# xc7z015unit3.net
KiCad netlist of a schematic drawn in Altium Designer
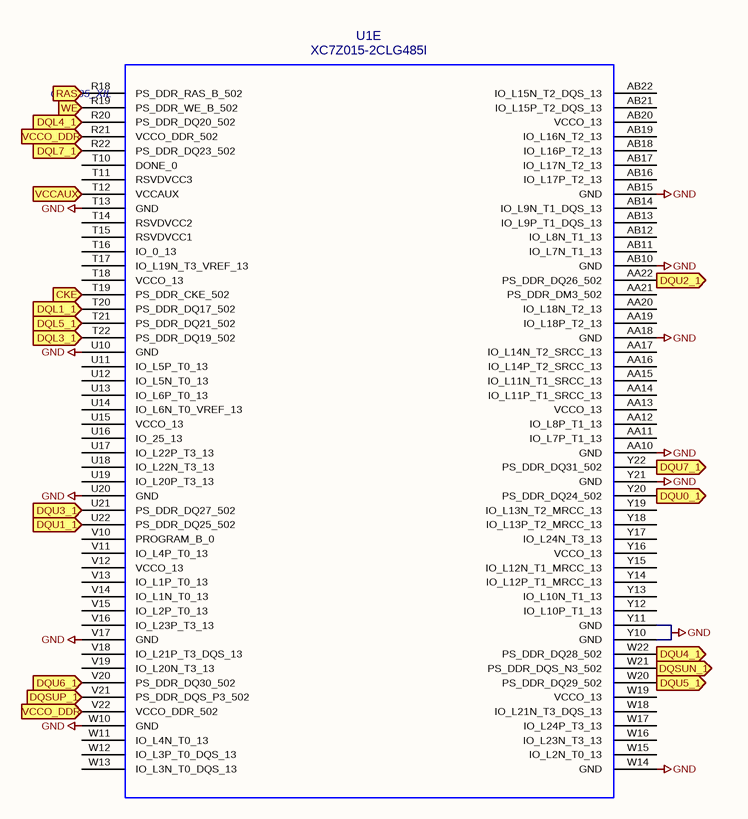
[diagram p0: xc7z015unit3.SchDoc]

(export (version "E")
  (design (tool "Eeschema 10.0.6"))
  (components
    (comp (ref "U1")
      (value "XC7Z015-2CLG485I")
      (footprint "CLG485_XIL")
      (libsource (lib "XC7Z015-CLG485") (part "XC7Z015-2CLG485I"))
    )
  )
  (nets
    (net (code "1") (name "/CKE") (class "Default")
      (node (ref "U1") (pin "T19") (pinfunction "PS_DDR_CKE_502_T19") (pintype "passive"))
    )
    (net (code "2") (name "/DQL1_1") (class "Default")
      (node (ref "U1") (pin "T20") (pinfunction "PS_DDR_DQ17_502_T20") (pintype "passive"))
    )
    (net (code "3") (name "/DQL3_1") (class "Default")
      (node (ref "U1") (pin "T22") (pinfunction "PS_DDR_DQ19_502_T22") (pintype "passive"))
    )
    (net (code "4") (name "/DQL4_1") (class "Default")
      (node (ref "U1") (pin "R20") (pinfunction "PS_DDR_DQ20_502_R20") (pintype "passive"))
    )
    (net (code "5") (name "/DQL5_1") (class "Default")
      (node (ref "U1") (pin "T21") (pinfunction "PS_DDR_DQ21_502_T21") (pintype "passive"))
    )
    (net (code "6") (name "/DQL7_1") (class "Default")
      (node (ref "U1") (pin "R22") (pinfunction "PS_DDR_DQ23_502_R22") (pintype "passive"))
    )
    (net (code "7") (name "/DQSUN_1") (class "Default")
      (node (ref "U1") (pin "W21") (pinfunction "PS_DDR_DQS_N3_502_W21") (pintype "passive"))
    )
    (net (code "8") (name "/DQSUP_1") (class "Default")
      (node (ref "U1") (pin "V21") (pinfunction "PS_DDR_DQS_P3_502_V21") (pintype "passive"))
    )
    (net (code "9") (name "/DQU0_1") (class "Default")
      (node (ref "U1") (pin "Y20") (pinfunction "PS_DDR_DQ24_502_Y20") (pintype "passive"))
    )
    (net (code "10") (name "/DQU1_1") (class "Default")
      (node (ref "U1") (pin "U22") (pinfunction "PS_DDR_DQ25_502_U22") (pintype "passive"))
    )
    (net (code "11") (name "/DQU2_1") (class "Default")
      (node (ref "U1") (pin "AA22") (pinfunction "PS_DDR_DQ26_502_AA22") (pintype "passive"))
    )
    (net (code "12") (name "/DQU3_1") (class "Default")
      (node (ref "U1") (pin "U21") (pinfunction "PS_DDR_DQ27_502_U21") (pintype "passive"))
    )
    (net (code "13") (name "/DQU4_1") (class "Default")
      (node (ref "U1") (pin "W22") (pinfunction "PS_DDR_DQ28_502_W22") (pintype "passive"))
    )
    (net (code "14") (name "/DQU5_1") (class "Default")
      (node (ref "U1") (pin "W20") (pinfunction "PS_DDR_DQ29_502_W20") (pintype "passive"))
    )
    (net (code "15") (name "/DQU6_1") (class "Default")
      (node (ref "U1") (pin "V20") (pinfunction "PS_DDR_DQ30_502_V20") (pintype "passive"))
    )
    (net (code "16") (name "/DQU7_1") (class "Default")
      (node (ref "U1") (pin "Y22") (pinfunction "PS_DDR_DQ31_502_Y22") (pintype "passive"))
    )
    (net (code "17") (name "/RAS") (class "Default")
      (node (ref "U1") (pin "R18") (pinfunction "PS_DDR_RAS_B_502_R18") (pintype "passive"))
    )
    (net (code "18") (name "/VCCAUX") (class "Default")
      (node (ref "U1") (pin "T12") (pinfunction "VCCAUX_T12") (pintype "passive"))
    )
    (net (code "19") (name "/VCCO_DDR") (class "Default")
      (node (ref "U1") (pin "R21") (pinfunction "VCCO_DDR_502_R21") (pintype "passive"))
      (node (ref "U1") (pin "V22") (pinfunction "VCCO_DDR_502_V22") (pintype "passive"))
    )
    (net (code "20") (name "/WE") (class "Default")
      (node (ref "U1") (pin "R19") (pinfunction "PS_DDR_WE_B_502_R19") (pintype "passive"))
    )
    (net (code "21") (name "GND") (class "Default")
      (node (ref "U1") (pin "AA10") (pinfunction "GND_AA10") (pintype "passive"))
      (node (ref "U1") (pin "AA18") (pinfunction "GND_AA18") (pintype "passive"))
      (node (ref "U1") (pin "AB10") (pinfunction "GND_AB10") (pintype "passive"))
      (node (ref "U1") (pin "AB15") (pinfunction "GND_AB15") (pintype "passive"))
      (node (ref "U1") (pin "T13") (pinfunction "GND_T13") (pintype "passive"))
      (node (ref "U1") (pin "U10") (pinfunction "GND_U10") (pintype "passive"))
      (node (ref "U1") (pin "U20") (pinfunction "GND_U20") (pintype "passive"))
      (node (ref "U1") (pin "V17") (pinfunction "GND_V17") (pintype "passive"))
      (node (ref "U1") (pin "W10") (pinfunction "GND_W10") (pintype "passive"))
      (node (ref "U1") (pin "W14") (pinfunction "GND_W14") (pintype "passive"))
      (node (ref "U1") (pin "Y10") (pinfunction "GND_Y10") (pintype "passive"))
      (node (ref "U1") (pin "Y11") (pinfunction "GND_Y11") (pintype "passive"))
      (node (ref "U1") (pin "Y21") (pinfunction "GND_Y21") (pintype "passive"))
    )
    (net (code "22") (name "unconnected-(U1E-DONE_0-PadT10)") (class "Default")
      (node (ref "U1") (pin "T10") (pinfunction "DONE_0_T10") (pintype "passive"))
    )
    (net (code "23") (name "unconnected-(U1E-IO_0_13-PadT16)") (class "Default")
      (node (ref "U1") (pin "T16") (pinfunction "IO_0_13_T16") (pintype "passive"))
    )
    (net (code "24") (name "unconnected-(U1E-IO_25_13-PadU16)") (class "Default")
      (node (ref "U1") (pin "U16") (pinfunction "IO_25_13_U16") (pintype "passive"))
    )
    (net (code "25") (name "unconnected-(U1E-IO_L1N_T0_13-PadV14)") (class "Default")
      (node (ref "U1") (pin "V14") (pinfunction "IO_L1N_T0_13_V14") (pintype "passive"))
    )
    (net (code "26") (name "unconnected-(U1E-IO_L1P_T0_13-PadV13)") (class "Default")
      (node (ref "U1") (pin "V13") (pinfunction "IO_L1P_T0_13_V13") (pintype "passive"))
    )
    (net (code "27") (name "unconnected-(U1E-IO_L2N_T0_13-PadW15)") (class "Default")
      (node (ref "U1") (pin "W15") (pinfunction "IO_L2N_T0_13_W15") (pintype "passive"))
    )
    (net (code "28") (name "unconnected-(U1E-IO_L2P_T0_13-PadV15)") (class "Default")
      (node (ref "U1") (pin "V15") (pinfunction "IO_L2P_T0_13_V15") (pintype "passive"))
    )
    (net (code "29") (name "unconnected-(U1E-IO_L3N_T0_DQS_13-PadW13)") (class "Default")
      (node (ref "U1") (pin "W13") (pinfunction "IO_L3N_T0_DQS_13_W13") (pintype "passive"))
    )
    (net (code "30") (name "unconnected-(U1E-IO_L3P_T0_DQS_13-PadW12)") (class "Default")
      (node (ref "U1") (pin "W12") (pinfunction "IO_L3P_T0_DQS_13_W12") (pintype "passive"))
    )
    (net (code "31") (name "unconnected-(U1E-IO_L4N_T0_13-PadW11)") (class "Default")
      (node (ref "U1") (pin "W11") (pinfunction "IO_L4N_T0_13_W11") (pintype "passive"))
    )
    (net (code "32") (name "unconnected-(U1E-IO_L4P_T0_13-PadV11)") (class "Default")
      (node (ref "U1") (pin "V11") (pinfunction "IO_L4P_T0_13_V11") (pintype "passive"))
    )
    (net (code "33") (name "unconnected-(U1E-IO_L5N_T0_13-PadU12)") (class "Default")
      (node (ref "U1") (pin "U12") (pinfunction "IO_L5N_T0_13_U12") (pintype "passive"))
    )
    (net (code "34") (name "unconnected-(U1E-IO_L5P_T0_13-PadU11)") (class "Default")
      (node (ref "U1") (pin "U11") (pinfunction "IO_L5P_T0_13_U11") (pintype "passive"))
    )
    (net (code "35") (name "unconnected-(U1E-IO_L6N_T0_VREF_13-PadU14)") (class "Default")
      (node (ref "U1") (pin "U14") (pinfunction "IO_L6N_T0_VREF_13_U14") (pintype "passive"))
    )
    (net (code "36") (name "unconnected-(U1E-IO_L6P_T0_13-PadU13)") (class "Default")
      (node (ref "U1") (pin "U13") (pinfunction "IO_L6P_T0_13_U13") (pintype "passive"))
    )
    (net (code "37") (name "unconnected-(U1E-IO_L7N_T1_13-PadAB11)") (class "Default")
      (node (ref "U1") (pin "AB11") (pinfunction "IO_L7N_T1_13_AB11") (pintype "passive"))
    )
    (net (code "38") (name "unconnected-(U1E-IO_L7P_T1_13-PadAA11)") (class "Default")
      (node (ref "U1") (pin "AA11") (pinfunction "IO_L7P_T1_13_AA11") (pintype "passive"))
    )
    (net (code "39") (name "unconnected-(U1E-IO_L8N_T1_13-PadAB12)") (class "Default")
      (node (ref "U1") (pin "AB12") (pinfunction "IO_L8N_T1_13_AB12") (pintype "passive"))
    )
    (net (code "40") (name "unconnected-(U1E-IO_L8P_T1_13-PadAA12)") (class "Default")
      (node (ref "U1") (pin "AA12") (pinfunction "IO_L8P_T1_13_AA12") (pintype "passive"))
    )
    (net (code "41") (name "unconnected-(U1E-IO_L9N_T1_DQS_13-PadAB14)") (class "Default")
      (node (ref "U1") (pin "AB14") (pinfunction "IO_L9N_T1_DQS_13_AB14") (pintype "passive"))
    )
    (net (code "42") (name "unconnected-(U1E-IO_L9P_T1_DQS_13-PadAB13)") (class "Default")
      (node (ref "U1") (pin "AB13") (pinfunction "IO_L9P_T1_DQS_13_AB13") (pintype "passive"))
    )
    (net (code "43") (name "unconnected-(U1E-IO_L10N_T1_13-PadY13)") (class "Default")
      (node (ref "U1") (pin "Y13") (pinfunction "IO_L10N_T1_13_Y13") (pintype "passive"))
    )
    (net (code "44") (name "unconnected-(U1E-IO_L10P_T1_13-PadY12)") (class "Default")
      (node (ref "U1") (pin "Y12") (pinfunction "IO_L10P_T1_13_Y12") (pintype "passive"))
    )
    (net (code "45") (name "unconnected-(U1E-IO_L11N_T1_SRCC_13-PadAA15)") (class "Default")
      (node (ref "U1") (pin "AA15") (pinfunction "IO_L11N_T1_SRCC_13_AA15") (pintype "passive"))
    )
    (net (code "46") (name "unconnected-(U1E-IO_L11P_T1_SRCC_13-PadAA14)") (class "Default")
      (node (ref "U1") (pin "AA14") (pinfunction "IO_L11P_T1_SRCC_13_AA14") (pintype "passive"))
    )
    (net (code "47") (name "unconnected-(U1E-IO_L12N_T1_MRCC_13-PadY15)") (class "Default")
      (node (ref "U1") (pin "Y15") (pinfunction "IO_L12N_T1_MRCC_13_Y15") (pintype "passive"))
    )
    (net (code "48") (name "unconnected-(U1E-IO_L12P_T1_MRCC_13-PadY14)") (class "Default")
      (node (ref "U1") (pin "Y14") (pinfunction "IO_L12P_T1_MRCC_13_Y14") (pintype "passive"))
    )
    (net (code "49") (name "unconnected-(U1E-IO_L13N_T2_MRCC_13-PadY19)") (class "Default")
      (node (ref "U1") (pin "Y19") (pinfunction "IO_L13N_T2_MRCC_13_Y19") (pintype "passive"))
    )
    (net (code "50") (name "unconnected-(U1E-IO_L13P_T2_MRCC_13-PadY18)") (class "Default")
      (node (ref "U1") (pin "Y18") (pinfunction "IO_L13P_T2_MRCC_13_Y18") (pintype "passive"))
    )
    (net (code "51") (name "unconnected-(U1E-IO_L14N_T2_SRCC_13-PadAA17)") (class "Default")
      (node (ref "U1") (pin "AA17") (pinfunction "IO_L14N_T2_SRCC_13_AA17") (pintype "passive"))
    )
    (net (code "52") (name "unconnected-(U1E-IO_L14P_T2_SRCC_13-PadAA16)") (class "Default")
      (node (ref "U1") (pin "AA16") (pinfunction "IO_L14P_T2_SRCC_13_AA16") (pintype "passive"))
    )
    (net (code "53") (name "unconnected-(U1E-IO_L15N_T2_DQS_13-PadAB22)") (class "Default")
      (node (ref "U1") (pin "AB22") (pinfunction "IO_L15N_T2_DQS_13_AB22") (pintype "passive"))
    )
    (net (code "54") (name "unconnected-(U1E-IO_L15P_T2_DQS_13-PadAB21)") (class "Default")
      (node (ref "U1") (pin "AB21") (pinfunction "IO_L15P_T2_DQS_13_AB21") (pintype "passive"))
    )
    (net (code "55") (name "unconnected-(U1E-IO_L16N_T2_13-PadAB19)") (class "Default")
      (node (ref "U1") (pin "AB19") (pinfunction "IO_L16N_T2_13_AB19") (pintype "passive"))
    )
    (net (code "56") (name "unconnected-(U1E-IO_L16P_T2_13-PadAB18)") (class "Default")
      (node (ref "U1") (pin "AB18") (pinfunction "IO_L16P_T2_13_AB18") (pintype "passive"))
    )
    (net (code "57") (name "unconnected-(U1E-IO_L17N_T2_13-PadAB17)") (class "Default")
      (node (ref "U1") (pin "AB17") (pinfunction "IO_L17N_T2_13_AB17") (pintype "passive"))
    )
    (net (code "58") (name "unconnected-(U1E-IO_L17P_T2_13-PadAB16)") (class "Default")
      (node (ref "U1") (pin "AB16") (pinfunction "IO_L17P_T2_13_AB16") (pintype "passive"))
    )
    (net (code "59") (name "unconnected-(U1E-IO_L18N_T2_13-PadAA20)") (class "Default")
      (node (ref "U1") (pin "AA20") (pinfunction "IO_L18N_T2_13_AA20") (pintype "passive"))
    )
    (net (code "60") (name "unconnected-(U1E-IO_L18P_T2_13-PadAA19)") (class "Default")
      (node (ref "U1") (pin "AA19") (pinfunction "IO_L18P_T2_13_AA19") (pintype "passive"))
    )
    (net (code "61") (name "unconnected-(U1E-IO_L19N_T3_VREF_13-PadT17)") (class "Default")
      (node (ref "U1") (pin "T17") (pinfunction "IO_L19N_T3_VREF_13_T17") (pintype "passive"))
    )
    (net (code "62") (name "unconnected-(U1E-IO_L20N_T3_13-PadV19)") (class "Default")
      (node (ref "U1") (pin "V19") (pinfunction "IO_L20N_T3_13_V19") (pintype "passive"))
    )
    (net (code "63") (name "unconnected-(U1E-IO_L20P_T3_13-PadU19)") (class "Default")
      (node (ref "U1") (pin "U19") (pinfunction "IO_L20P_T3_13_U19") (pintype "passive"))
    )
    (net (code "64") (name "unconnected-(U1E-IO_L21N_T3_DQS_13-PadW18)") (class "Default")
      (node (ref "U1") (pin "W18") (pinfunction "IO_L21N_T3_DQS_13_W18") (pintype "passive"))
    )
    (net (code "65") (name "unconnected-(U1E-IO_L21P_T3_DQS_13-PadV18)") (class "Default")
      (node (ref "U1") (pin "V18") (pinfunction "IO_L21P_T3_DQS_13_V18") (pintype "passive"))
    )
    (net (code "66") (name "unconnected-(U1E-IO_L22N_T3_13-PadU18)") (class "Default")
      (node (ref "U1") (pin "U18") (pinfunction "IO_L22N_T3_13_U18") (pintype "passive"))
    )
    (net (code "67") (name "unconnected-(U1E-IO_L22P_T3_13-PadU17)") (class "Default")
      (node (ref "U1") (pin "U17") (pinfunction "IO_L22P_T3_13_U17") (pintype "passive"))
    )
    (net (code "68") (name "unconnected-(U1E-IO_L23N_T3_13-PadW16)") (class "Default")
      (node (ref "U1") (pin "W16") (pinfunction "IO_L23N_T3_13_W16") (pintype "passive"))
    )
    (net (code "69") (name "unconnected-(U1E-IO_L23P_T3_13-PadV16)") (class "Default")
      (node (ref "U1") (pin "V16") (pinfunction "IO_L23P_T3_13_V16") (pintype "passive"))
    )
    (net (code "70") (name "unconnected-(U1E-IO_L24N_T3_13-PadY17)") (class "Default")
      (node (ref "U1") (pin "Y17") (pinfunction "IO_L24N_T3_13_Y17") (pintype "passive"))
    )
    (net (code "71") (name "unconnected-(U1E-IO_L24P_T3_13-PadW17)") (class "Default")
      (node (ref "U1") (pin "W17") (pinfunction "IO_L24P_T3_13_W17") (pintype "passive"))
    )
    (net (code "72") (name "unconnected-(U1E-PROGRAM_B_0-PadV10)") (class "Default")
      (node (ref "U1") (pin "V10") (pinfunction "PROGRAM_B_0_V10") (pintype "passive"))
    )
    (net (code "73") (name "unconnected-(U1E-PS_DDR_DM3_502-PadAA21)") (class "Default")
      (node (ref "U1") (pin "AA21") (pinfunction "PS_DDR_DM3_502_AA21") (pintype "passive"))
    )
    (net (code "74") (name "unconnected-(U1E-RSVDVCC1-PadT15)") (class "Default")
      (node (ref "U1") (pin "T15") (pinfunction "RSVDVCC1_T15") (pintype "passive"))
    )
    (net (code "75") (name "unconnected-(U1E-RSVDVCC2-PadT14)") (class "Default")
      (node (ref "U1") (pin "T14") (pinfunction "RSVDVCC2_T14") (pintype "passive"))
    )
    (net (code "76") (name "unconnected-(U1E-RSVDVCC3-PadT11)") (class "Default")
      (node (ref "U1") (pin "T11") (pinfunction "RSVDVCC3_T11") (pintype "passive"))
    )
    (net (code "77") (name "unconnected-(U1E-VCCO_13-PadAA13)") (class "Default")
      (node (ref "U1") (pin "AA13") (pinfunction "VCCO_13_AA13") (pintype "passive"))
    )
    (net (code "78") (name "unconnected-(U1E-VCCO_13-PadAB20)") (class "Default")
      (node (ref "U1") (pin "AB20") (pinfunction "VCCO_13_AB20") (pintype "passive"))
    )
    (net (code "79") (name "unconnected-(U1E-VCCO_13-PadT18)") (class "Default")
      (node (ref "U1") (pin "T18") (pinfunction "VCCO_13_T18") (pintype "passive"))
    )
    (net (code "80") (name "unconnected-(U1E-VCCO_13-PadU15)") (class "Default")
      (node (ref "U1") (pin "U15") (pinfunction "VCCO_13_U15") (pintype "passive"))
    )
    (net (code "81") (name "unconnected-(U1E-VCCO_13-PadV12)") (class "Default")
      (node (ref "U1") (pin "V12") (pinfunction "VCCO_13_V12") (pintype "passive"))
    )
    (net (code "82") (name "unconnected-(U1E-VCCO_13-PadW19)") (class "Default")
      (node (ref "U1") (pin "W19") (pinfunction "VCCO_13_W19") (pintype "passive"))
    )
    (net (code "83") (name "unconnected-(U1E-VCCO_13-PadY16)") (class "Default")
      (node (ref "U1") (pin "Y16") (pinfunction "VCCO_13_Y16") (pintype "passive"))
    )
  )
)
